# garage.net
KiCad netlist of a schematic drawn in EAGLE
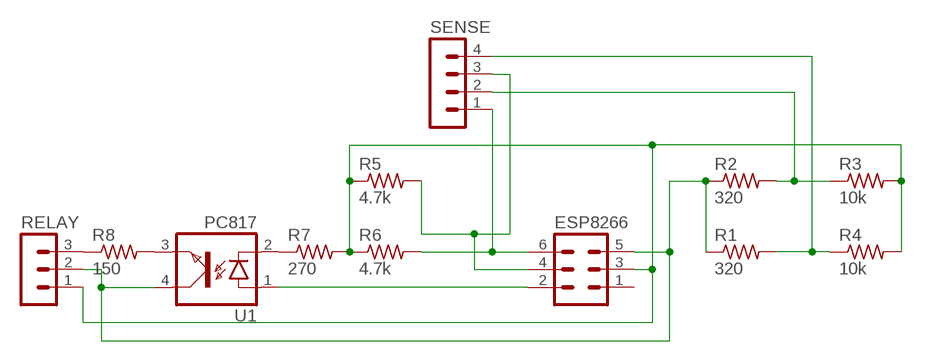
[diagram p0: schematic, sheet 1]

(export (version "E")
  (design (tool "Eeschema 10.0.6"))
  (components
    (comp (ref "ESP8266")
      (value "MA03-2")
      (footprint "eagle-import:MA03-2")
      (libsource (lib "eagle-import") (part "MA03-2"))
    )
    (comp (ref "R1")
      (value "320")
      (footprint "eagle-import:0207_2V")
      (libsource (lib "eagle-import") (part "R-US_0207/2V"))
    )
    (comp (ref "R2")
      (value "320")
      (footprint "eagle-import:0207_2V")
      (libsource (lib "eagle-import") (part "R-US_0207/2V"))
    )
    (comp (ref "R3")
      (value "10k")
      (footprint "eagle-import:0207_2V")
      (libsource (lib "eagle-import") (part "R-US_0207/2V"))
    )
    (comp (ref "R4")
      (value "10k")
      (footprint "eagle-import:0207_2V")
      (libsource (lib "eagle-import") (part "R-US_0207/2V"))
    )
    (comp (ref "R5")
      (value "4.7k")
      (footprint "eagle-import:0207_2V")
      (libsource (lib "eagle-import") (part "R-US_0207/2V"))
    )
    (comp (ref "R6")
      (value "4.7k")
      (footprint "eagle-import:0207_2V")
      (libsource (lib "eagle-import") (part "R-US_0207/2V"))
    )
    (comp (ref "R7")
      (value "270")
      (footprint "eagle-import:0207_2V")
      (libsource (lib "eagle-import") (part "R-US_0207/2V"))
    )
    (comp (ref "R8")
      (value "150")
      (footprint "eagle-import:0207_2V")
      (libsource (lib "eagle-import") (part "R-US_0207/2V"))
    )
    (comp (ref "RELAY")
      (value "MA03-1")
      (footprint "eagle-import:MA03-1")
      (libsource (lib "eagle-import") (part "MA03-1"))
    )
    (comp (ref "SENSE")
      (value "MA04-1")
      (footprint "eagle-import:MA04-1")
      (libsource (lib "eagle-import") (part "MA04-1"))
    )
    (comp (ref "U1")
      (value "PC817")
      (footprint "eagle-import:DIL04")
      (fields (field (name "MPN") "PC817X4J000F"))
      (libsource (lib "eagle-import") (part "PC817"))
    )
  )
  (nets
    (net (code "1") (name "Net-(ESP8266-Pad3)") (class "Default")
      (node (ref "ESP8266") (pin "3") (pinfunction "3_3") (pintype "passive"))
      (node (ref "R3") (pin "2") (pinfunction "2_2") (pintype "passive"))
      (node (ref "R4") (pin "2") (pinfunction "2_2") (pintype "passive"))
      (node (ref "R5") (pin "1") (pinfunction "1_1") (pintype "passive"))
      (node (ref "R6") (pin "1") (pinfunction "1_1") (pintype "passive"))
      (node (ref "R7") (pin "2") (pinfunction "2_2") (pintype "passive"))
      (node (ref "RELAY") (pin "1") (pinfunction "1_1") (pintype "passive"))
    )
    (net (code "2") (name "Net-(ESP8266-Pad4)") (class "Default")
      (node (ref "ESP8266") (pin "4") (pinfunction "4_4") (pintype "passive"))
      (node (ref "R5") (pin "2") (pinfunction "2_2") (pintype "passive"))
      (node (ref "SENSE") (pin "3") (pinfunction "3_3") (pintype "passive"))
    )
    (net (code "3") (name "Net-(ESP8266-Pad6)") (class "Default")
      (node (ref "ESP8266") (pin "6") (pinfunction "6_6") (pintype "passive"))
      (node (ref "R6") (pin "2") (pinfunction "2_2") (pintype "passive"))
      (node (ref "SENSE") (pin "1") (pinfunction "1_1") (pintype "passive"))
    )
    (net (code "4") (name "Net-(R1-Pad2)") (class "Default")
      (node (ref "R1") (pin "2") (pinfunction "2_2") (pintype "passive"))
      (node (ref "R4") (pin "1") (pinfunction "1_1") (pintype "passive"))
      (node (ref "SENSE") (pin "4") (pinfunction "4_4") (pintype "passive"))
    )
    (net (code "5") (name "Net-(R2-Pad2)") (class "Default")
      (node (ref "R2") (pin "2") (pinfunction "2_2") (pintype "passive"))
      (node (ref "R3") (pin "1") (pinfunction "1_1") (pintype "passive"))
      (node (ref "SENSE") (pin "2") (pinfunction "2_2") (pintype "passive"))
    )
    (net (code "6") (name "Net-(R8-Pad1)") (class "Default")
      (node (ref "R8") (pin "1") (pinfunction "1_1") (pintype "passive"))
      (node (ref "RELAY") (pin "3") (pinfunction "3_3") (pintype "passive"))
    )
    (net (code "7") (name "Net-(U1-A)") (class "Default")
      (node (ref "ESP8266") (pin "2") (pinfunction "2_2") (pintype "passive"))
      (node (ref "U1") (pin "1") (pinfunction "A_1") (pintype "passive"))
    )
    (net (code "8") (name "Net-(U1-C)") (class "Default")
      (node (ref "R7") (pin "1") (pinfunction "1_1") (pintype "passive"))
      (node (ref "U1") (pin "2") (pinfunction "C_2") (pintype "passive"))
    )
    (net (code "9") (name "Net-(U1-COL)") (class "Default")
      (node (ref "ESP8266") (pin "5") (pinfunction "5_5") (pintype "passive"))
      (node (ref "R1") (pin "1") (pinfunction "1_1") (pintype "passive"))
      (node (ref "R2") (pin "1") (pinfunction "1_1") (pintype "passive"))
      (node (ref "RELAY") (pin "2") (pinfunction "2_2") (pintype "passive"))
      (node (ref "U1") (pin "4") (pinfunction "COL_4") (pintype "passive"))
    )
    (net (code "10") (name "Net-(U1-EMIT)") (class "Default")
      (node (ref "R8") (pin "2") (pinfunction "2_2") (pintype "passive"))
      (node (ref "U1") (pin "3") (pinfunction "EMIT_3") (pintype "passive"))
    )
    (net (code "11") (name "unconnected-(ESP8266-Pad1)") (class "Default")
      (node (ref "ESP8266") (pin "1") (pinfunction "1_1") (pintype "passive"))
    )
  )
)
